# XOR.net
KiCad netlist of a schematic drawn in EAGLE
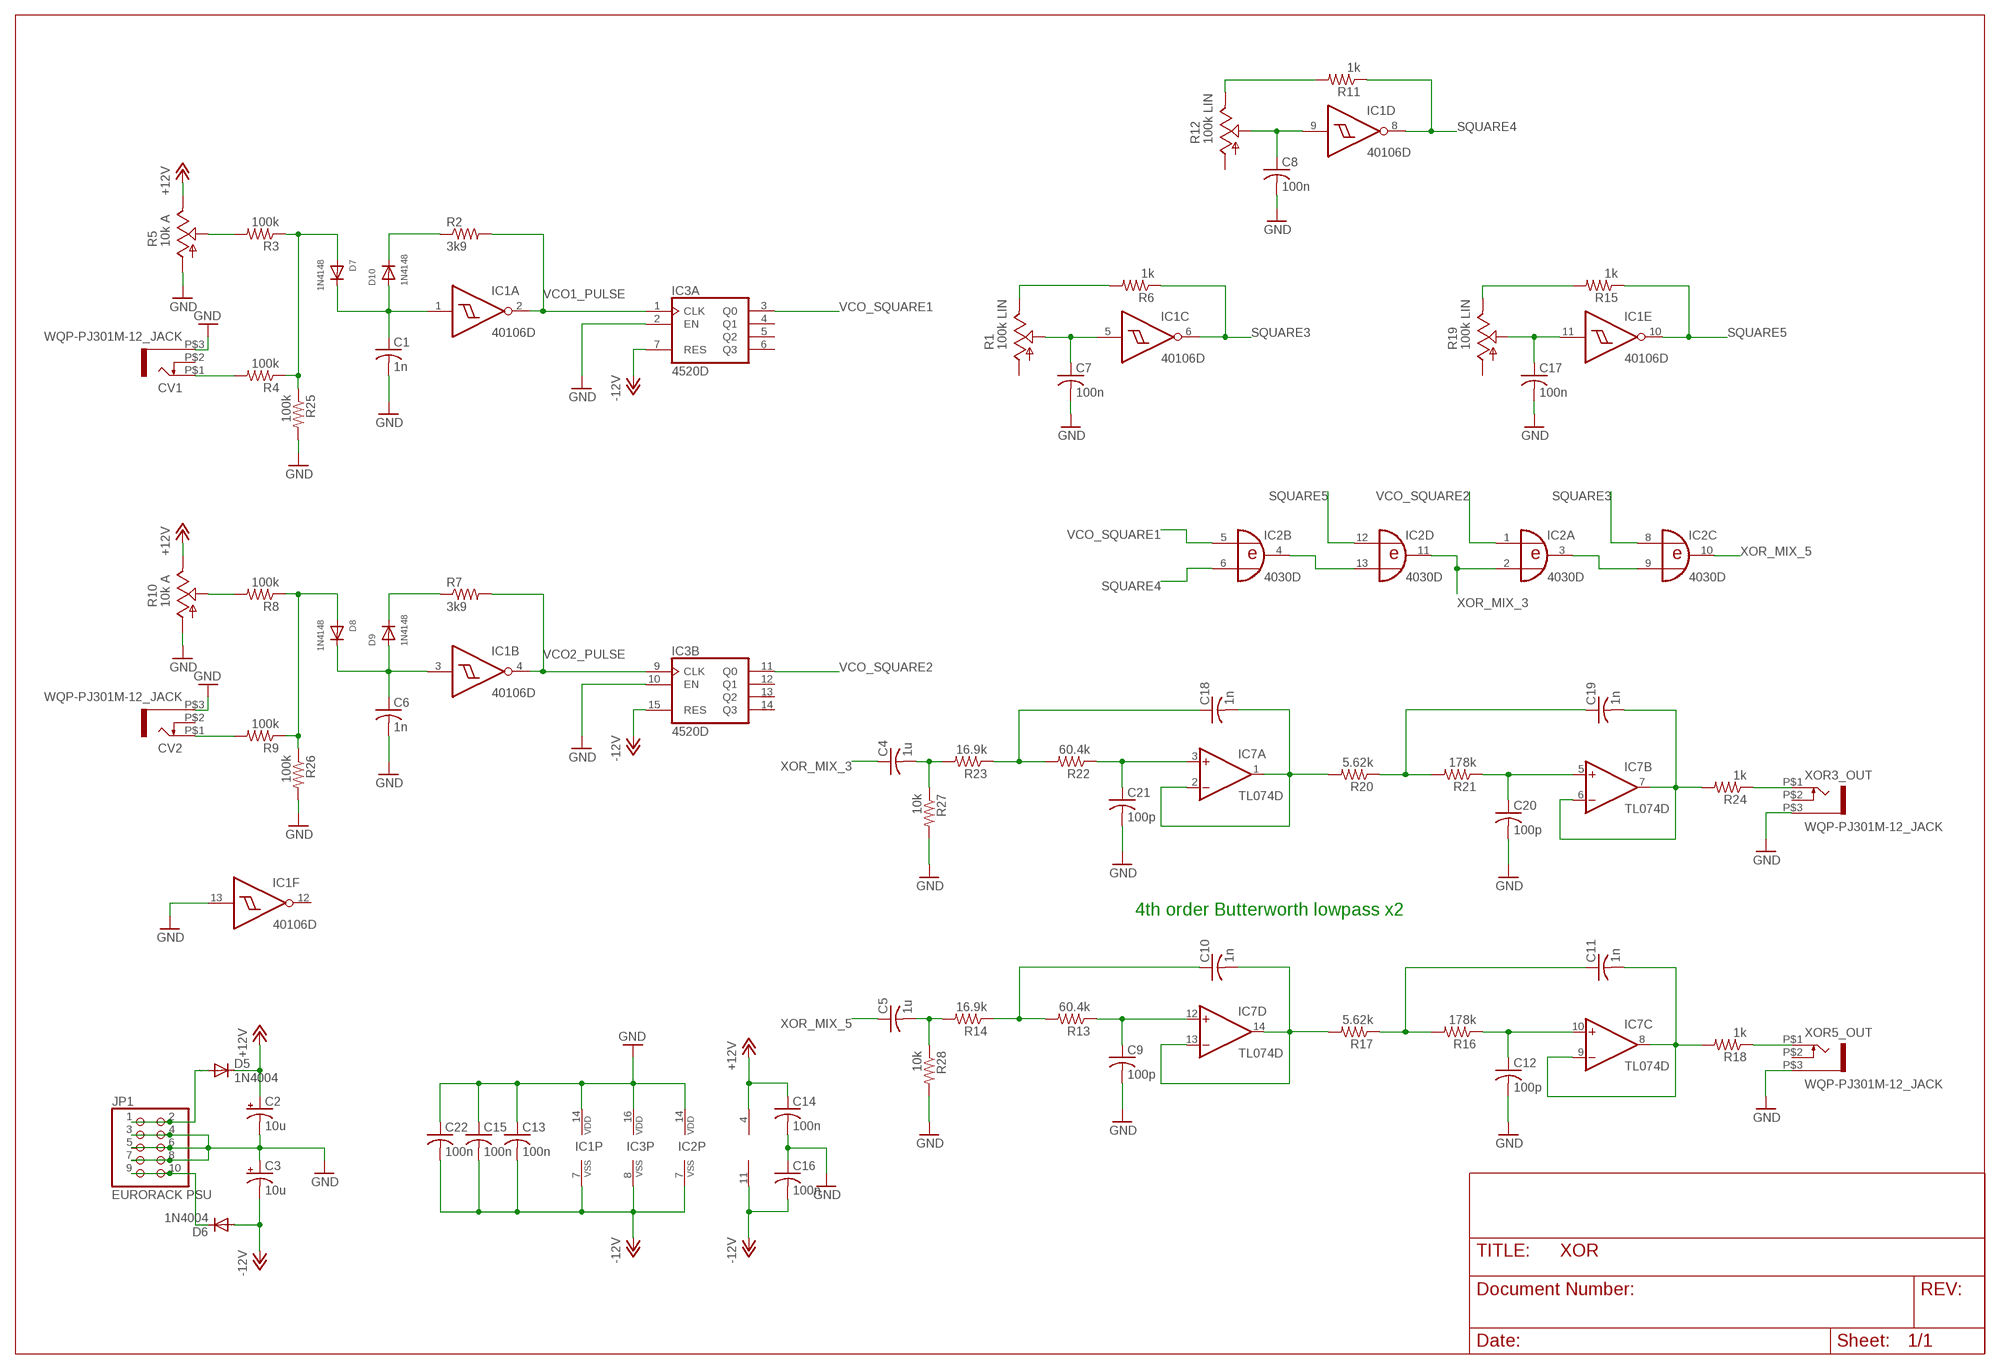
[diagram p0: schematic, sheet 1]

(export (version "E")
  (design (tool "Eeschema 10.0.6"))
  (components
    (comp (ref "C1")
      (value "1n")
      (footprint "eagle-import:C0603K")
      (libsource (lib "eagle-import") (part "C-USC0603K"))
    )
    (comp (ref "C2")
      (value "10u")
      (footprint "eagle-import:PANASONIC_D")
      (libsource (lib "eagle-import") (part "CPOL-USD"))
    )
    (comp (ref "C3")
      (value "10u")
      (footprint "eagle-import:PANASONIC_D")
      (libsource (lib "eagle-import") (part "CPOL-USD"))
    )
    (comp (ref "C4")
      (value "1u")
      (footprint "eagle-import:C0603K")
      (libsource (lib "eagle-import") (part "C-USC0603K"))
    )
    (comp (ref "C5")
      (value "1u")
      (footprint "eagle-import:C0603K")
      (libsource (lib "eagle-import") (part "C-USC0603K"))
    )
    (comp (ref "C6")
      (value "1n")
      (footprint "eagle-import:C0603K")
      (libsource (lib "eagle-import") (part "C-USC0603K"))
    )
    (comp (ref "C7")
      (value "100n")
      (footprint "eagle-import:C0603K")
      (libsource (lib "eagle-import") (part "C-USC0603K"))
    )
    (comp (ref "C8")
      (value "100n")
      (footprint "eagle-import:C0603K")
      (libsource (lib "eagle-import") (part "C-USC0603K"))
    )
    (comp (ref "C9")
      (value "100p")
      (footprint "eagle-import:C0603K")
      (libsource (lib "eagle-import") (part "C-USC0603K"))
    )
    (comp (ref "C10")
      (value "1n")
      (footprint "eagle-import:C0603K")
      (libsource (lib "eagle-import") (part "C-USC0603K"))
    )
    (comp (ref "C11")
      (value "1n")
      (footprint "eagle-import:C0603K")
      (libsource (lib "eagle-import") (part "C-USC0603K"))
    )
    (comp (ref "C12")
      (value "100p")
      (footprint "eagle-import:C0603K")
      (libsource (lib "eagle-import") (part "C-USC0603K"))
    )
    (comp (ref "C13")
      (value "100n")
      (footprint "eagle-import:C0603K")
      (libsource (lib "eagle-import") (part "C-USC0603K"))
    )
    (comp (ref "C14")
      (value "100n")
      (footprint "eagle-import:C0603K")
      (libsource (lib "eagle-import") (part "C-USC0603K"))
    )
    (comp (ref "C15")
      (value "100n")
      (footprint "eagle-import:C0603K")
      (libsource (lib "eagle-import") (part "C-USC0603K"))
    )
    (comp (ref "C16")
      (value "100n")
      (footprint "eagle-import:C0603K")
      (libsource (lib "eagle-import") (part "C-USC0603K"))
    )
    (comp (ref "C17")
      (value "100n")
      (footprint "eagle-import:C0603K")
      (libsource (lib "eagle-import") (part "C-USC0603K"))
    )
    (comp (ref "C18")
      (value "1n")
      (footprint "eagle-import:C0603K")
      (libsource (lib "eagle-import") (part "C-USC0603K"))
    )
    (comp (ref "C19")
      (value "1n")
      (footprint "eagle-import:C0603K")
      (libsource (lib "eagle-import") (part "C-USC0603K"))
    )
    (comp (ref "C20")
      (value "100p")
      (footprint "eagle-import:C0603K")
      (libsource (lib "eagle-import") (part "C-USC0603K"))
    )
    (comp (ref "C21")
      (value "100p")
      (footprint "eagle-import:C0603K")
      (libsource (lib "eagle-import") (part "C-USC0603K"))
    )
    (comp (ref "C22")
      (value "100n")
      (footprint "eagle-import:C0603K")
      (libsource (lib "eagle-import") (part "C-USC0603K"))
    )
    (comp (ref "CV1")
      (value "WQP-PJ301M-12_JACK")
      (footprint "eagle-import:WQP-PJ301M-12_JACK")
      (libsource (lib "eagle-import") (part "WQP-PJ301M-12_JACK"))
    )
    (comp (ref "CV2")
      (value "WQP-PJ301M-12_JACK")
      (footprint "eagle-import:WQP-PJ301M-12_JACK")
      (libsource (lib "eagle-import") (part "WQP-PJ301M-12_JACK"))
    )
    (comp (ref "D5")
      (value "1N4004")
      (footprint "eagle-import:DO214AA")
      (libsource (lib "eagle-import") (part "DIODE-DO214AA"))
    )
    (comp (ref "D6")
      (value "1N4004")
      (footprint "eagle-import:DO214AA")
      (libsource (lib "eagle-import") (part "DIODE-DO214AA"))
    )
    (comp (ref "D7")
      (value "1N4148")
      (footprint "eagle-import:SOD-323F")
      (libsource (lib "eagle-import") (part "DIODESOD-323F"))
    )
    (comp (ref "D8")
      (value "1N4148")
      (footprint "eagle-import:SOD-323F")
      (libsource (lib "eagle-import") (part "DIODESOD-323F"))
    )
    (comp (ref "D9")
      (value "1N4148")
      (footprint "eagle-import:SOD-323F")
      (libsource (lib "eagle-import") (part "DIODESOD-323F"))
    )
    (comp (ref "D10")
      (value "1N4148")
      (footprint "eagle-import:SOD-323F")
      (libsource (lib "eagle-import") (part "DIODESOD-323F"))
    )
    (comp (ref "IC1")
      (value "40106D")
      (footprint "eagle-import:SO14")
      (libsource (lib "eagle-import") (part "40106D"))
    )
    (comp (ref "IC2")
      (value "4030D")
      (footprint "eagle-import:SO14")
      (libsource (lib "eagle-import") (part "4030D"))
    )
    (comp (ref "IC3")
      (value "4520D")
      (footprint "eagle-import:SO16")
      (libsource (lib "eagle-import") (part "4520D"))
    )
    (comp (ref "IC7")
      (value "TL074D")
      (footprint "eagle-import:SO14")
      (libsource (lib "eagle-import") (part "TL074D"))
    )
    (comp (ref "JP1")
      (value "EURORACK PSU")
      (footprint "eagle-import:2X05")
      (libsource (lib "eagle-import") (part "PINHD-2X5"))
    )
    (comp (ref "R1")
      (value "100k LIN")
      (footprint "eagle-import:ALPS_POT_VERTICAL")
      (libsource (lib "eagle-import") (part "POT_USVERTICAL"))
    )
    (comp (ref "R2")
      (value "3k9")
      (footprint "eagle-import:R0603")
      (libsource (lib "eagle-import") (part "R-US_R0603"))
    )
    (comp (ref "R3")
      (value "100k")
      (footprint "eagle-import:R0603")
      (libsource (lib "eagle-import") (part "R-US_R0603"))
    )
    (comp (ref "R4")
      (value "100k")
      (footprint "eagle-import:R0603")
      (libsource (lib "eagle-import") (part "R-US_R0603"))
    )
    (comp (ref "R5")
      (value "10k A")
      (footprint "eagle-import:ALPS_POT_VERTICAL")
      (libsource (lib "eagle-import") (part "POT_USVERTICAL"))
    )
    (comp (ref "R6")
      (value "1k")
      (footprint "eagle-import:R0603")
      (libsource (lib "eagle-import") (part "R-US_R0603"))
    )
    (comp (ref "R7")
      (value "3k9")
      (footprint "eagle-import:R0603")
      (libsource (lib "eagle-import") (part "R-US_R0603"))
    )
    (comp (ref "R8")
      (value "100k")
      (footprint "eagle-import:R0603")
      (libsource (lib "eagle-import") (part "R-US_R0603"))
    )
    (comp (ref "R9")
      (value "100k")
      (footprint "eagle-import:R0603")
      (libsource (lib "eagle-import") (part "R-US_R0603"))
    )
    (comp (ref "R10")
      (value "10k A")
      (footprint "eagle-import:ALPS_POT_VERTICAL")
      (libsource (lib "eagle-import") (part "POT_USVERTICAL"))
    )
    (comp (ref "R11")
      (value "1k")
      (footprint "eagle-import:R0603")
      (libsource (lib "eagle-import") (part "R-US_R0603"))
    )
    (comp (ref "R12")
      (value "100k LIN")
      (footprint "eagle-import:ALPS_POT_VERTICAL")
      (libsource (lib "eagle-import") (part "POT_USVERTICAL"))
    )
    (comp (ref "R13")
      (value "60.4k")
      (footprint "eagle-import:R0603")
      (libsource (lib "eagle-import") (part "R-US_R0603"))
    )
    (comp (ref "R14")
      (value "16.9k")
      (footprint "eagle-import:R0603")
      (libsource (lib "eagle-import") (part "R-US_R0603"))
    )
    (comp (ref "R15")
      (value "1k")
      (footprint "eagle-import:R0603")
      (libsource (lib "eagle-import") (part "R-US_R0603"))
    )
    (comp (ref "R16")
      (value "178k")
      (footprint "eagle-import:R0603")
      (libsource (lib "eagle-import") (part "R-US_R0603"))
    )
    (comp (ref "R17")
      (value "5.62k")
      (footprint "eagle-import:R0603")
      (libsource (lib "eagle-import") (part "R-US_R0603"))
    )
    (comp (ref "R18")
      (value "1k")
      (footprint "eagle-import:R0603")
      (libsource (lib "eagle-import") (part "R-US_R0603"))
    )
    (comp (ref "R19")
      (value "100k LIN")
      (footprint "eagle-import:ALPS_POT_VERTICAL")
      (libsource (lib "eagle-import") (part "POT_USVERTICAL"))
    )
    (comp (ref "R20")
      (value "5.62k")
      (footprint "eagle-import:R0603")
      (libsource (lib "eagle-import") (part "R-US_R0603"))
    )
    (comp (ref "R21")
      (value "178k")
      (footprint "eagle-import:R0603")
      (libsource (lib "eagle-import") (part "R-US_R0603"))
    )
    (comp (ref "R22")
      (value "60.4k")
      (footprint "eagle-import:R0603")
      (libsource (lib "eagle-import") (part "R-US_R0603"))
    )
    (comp (ref "R23")
      (value "16.9k")
      (footprint "eagle-import:R0603")
      (libsource (lib "eagle-import") (part "R-US_R0603"))
    )
    (comp (ref "R24")
      (value "1k")
      (footprint "eagle-import:R0603")
      (libsource (lib "eagle-import") (part "R-US_R0603"))
    )
    (comp (ref "R25")
      (value "100k")
      (footprint "eagle-import:R0603")
      (libsource (lib "eagle-import") (part "R-US_R0603"))
    )
    (comp (ref "R26")
      (value "100k")
      (footprint "eagle-import:R0603")
      (libsource (lib "eagle-import") (part "R-US_R0603"))
    )
    (comp (ref "R27")
      (value "10k")
      (footprint "eagle-import:R0603")
      (libsource (lib "eagle-import") (part "R-US_R0603"))
    )
    (comp (ref "R28")
      (value "10k")
      (footprint "eagle-import:R0603")
      (libsource (lib "eagle-import") (part "R-US_R0603"))
    )
    (comp (ref "XOR3_OUT")
      (value "WQP-PJ301M-12_JACK")
      (footprint "eagle-import:WQP-PJ301M-12_JACK")
      (libsource (lib "eagle-import") (part "WQP-PJ301M-12_JACK"))
    )
    (comp (ref "XOR5_OUT")
      (value "WQP-PJ301M-12_JACK")
      (footprint "eagle-import:WQP-PJ301M-12_JACK")
      (libsource (lib "eagle-import") (part "WQP-PJ301M-12_JACK"))
    )
  )
  (nets
    (net (code "1") (name "+12V") (class "Default")
      (node (ref "C14") (pin "1") (pinfunction "1_1") (pintype "passive"))
      (node (ref "C2") (pin "+") (pinfunction "+_+") (pintype "passive"))
      (node (ref "D5") (pin "C") (pinfunction "C_C") (pintype "passive"))
      (node (ref "IC7") (pin "4") (pinfunction "V+_4") (pintype "power_in"))
      (node (ref "R10") (pin "P$1") (pinfunction "E_P$1") (pintype "passive"))
      (node (ref "R5") (pin "P$1") (pinfunction "E_P$1") (pintype "passive"))
    )
    (net (code "2") (name "-12V") (class "Default")
      (node (ref "C13") (pin "2") (pinfunction "2_2") (pintype "passive"))
      (node (ref "C15") (pin "2") (pinfunction "2_2") (pintype "passive"))
      (node (ref "C16") (pin "2") (pinfunction "2_2") (pintype "passive"))
      (node (ref "C22") (pin "2") (pinfunction "2_2") (pintype "passive"))
      (node (ref "C3") (pin "-") (pinfunction "-_-") (pintype "passive"))
      (node (ref "D6") (pin "A") (pinfunction "A_A") (pintype "passive"))
      (node (ref "IC1") (pin "7") (pinfunction "VSS_7") (pintype "power_in"))
      (node (ref "IC2") (pin "7") (pinfunction "VSS_7") (pintype "power_in"))
      (node (ref "IC3") (pin "15") (pinfunction "RES_15") (pintype "input"))
      (node (ref "IC3") (pin "7") (pinfunction "RES_7") (pintype "input"))
      (node (ref "IC3") (pin "8") (pinfunction "VSS_8") (pintype "power_in"))
      (node (ref "IC7") (pin "11") (pinfunction "V-_11") (pintype "power_in"))
    )
    (net (code "3") (name "/SQUARE3") (class "Default")
      (node (ref "IC1") (pin "6") (pinfunction "O_6") (pintype "output"))
      (node (ref "IC2") (pin "8") (pinfunction "I0_8") (pintype "input"))
      (node (ref "R6") (pin "1") (pinfunction "1_1") (pintype "passive"))
    )
    (net (code "4") (name "/SQUARE4") (class "Default")
      (node (ref "IC1") (pin "8") (pinfunction "O_8") (pintype "output"))
      (node (ref "IC2") (pin "6") (pinfunction "I1_6") (pintype "input"))
      (node (ref "R11") (pin "1") (pinfunction "1_1") (pintype "passive"))
    )
    (net (code "5") (name "/SQUARE5") (class "Default")
      (node (ref "IC1") (pin "10") (pinfunction "O_10") (pintype "output"))
      (node (ref "IC2") (pin "12") (pinfunction "I0_12") (pintype "input"))
      (node (ref "R15") (pin "1") (pinfunction "1_1") (pintype "passive"))
    )
    (net (code "6") (name "/VCO1_PULSE") (class "Default")
      (node (ref "IC1") (pin "2") (pinfunction "O_2") (pintype "output"))
      (node (ref "IC3") (pin "1") (pinfunction "CLK_1") (pintype "input"))
      (node (ref "R2") (pin "2") (pinfunction "2_2") (pintype "passive"))
    )
    (net (code "7") (name "/VCO2_PULSE") (class "Default")
      (node (ref "IC1") (pin "4") (pinfunction "O_4") (pintype "output"))
      (node (ref "IC3") (pin "9") (pinfunction "CLK_9") (pintype "input"))
      (node (ref "R7") (pin "2") (pinfunction "2_2") (pintype "passive"))
    )
    (net (code "8") (name "/VCO_SQUARE1") (class "Default")
      (node (ref "IC2") (pin "5") (pinfunction "I0_5") (pintype "input"))
      (node (ref "IC3") (pin "3") (pinfunction "Q0_3") (pintype "output"))
    )
    (net (code "9") (name "/VCO_SQUARE2") (class "Default")
      (node (ref "IC2") (pin "1") (pinfunction "I0_1") (pintype "input"))
      (node (ref "IC3") (pin "11") (pinfunction "Q0_11") (pintype "output"))
    )
    (net (code "10") (name "/XOR_MIX_3") (class "Default")
      (node (ref "C4") (pin "1") (pinfunction "1_1") (pintype "passive"))
      (node (ref "IC2") (pin "11") (pinfunction "O_11") (pintype "output"))
      (node (ref "IC2") (pin "2") (pinfunction "I1_2") (pintype "input"))
    )
    (net (code "11") (name "/XOR_MIX_5") (class "Default")
      (node (ref "C5") (pin "1") (pinfunction "1_1") (pintype "passive"))
      (node (ref "IC2") (pin "10") (pinfunction "O_10") (pintype "output"))
    )
    (net (code "12") (name "GND") (class "Default")
      (node (ref "C1") (pin "2") (pinfunction "2_2") (pintype "passive"))
      (node (ref "C12") (pin "2") (pinfunction "2_2") (pintype "passive"))
      (node (ref "C13") (pin "1") (pinfunction "1_1") (pintype "passive"))
      (node (ref "C14") (pin "2") (pinfunction "2_2") (pintype "passive"))
      (node (ref "C15") (pin "1") (pinfunction "1_1") (pintype "passive"))
      (node (ref "C16") (pin "1") (pinfunction "1_1") (pintype "passive"))
      (node (ref "C17") (pin "2") (pinfunction "2_2") (pintype "passive"))
      (node (ref "C2") (pin "-") (pinfunction "-_-") (pintype "passive"))
      (node (ref "C20") (pin "2") (pinfunction "2_2") (pintype "passive"))
      (node (ref "C21") (pin "2") (pinfunction "2_2") (pintype "passive"))
      (node (ref "C22") (pin "1") (pinfunction "1_1") (pintype "passive"))
      (node (ref "C3") (pin "+") (pinfunction "+_+") (pintype "passive"))
      (node (ref "C6") (pin "2") (pinfunction "2_2") (pintype "passive"))
      (node (ref "C7") (pin "2") (pinfunction "2_2") (pintype "passive"))
      (node (ref "C8") (pin "2") (pinfunction "2_2") (pintype "passive"))
      (node (ref "C9") (pin "2") (pinfunction "2_2") (pintype "passive"))
      (node (ref "CV1") (pin "P$3") (pinfunction "1_P$3") (pintype "passive"))
      (node (ref "CV2") (pin "P$3") (pinfunction "1_P$3") (pintype "passive"))
      (node (ref "IC1") (pin "13") (pinfunction "I_13") (pintype "input"))
      (node (ref "IC1") (pin "14") (pinfunction "VDD_14") (pintype "power_in"))
      (node (ref "IC2") (pin "14") (pinfunction "VDD_14") (pintype "power_in"))
      (node (ref "IC3") (pin "10") (pinfunction "EN_10") (pintype "input"))
      (node (ref "IC3") (pin "16") (pinfunction "VDD_16") (pintype "power_in"))
      (node (ref "IC3") (pin "2") (pinfunction "EN_2") (pintype "input"))
      (node (ref "JP1") (pin "3") (pinfunction "3_3") (pintype "passive"))
      (node (ref "JP1") (pin "4") (pinfunction "4_4") (pintype "passive"))
      (node (ref "JP1") (pin "5") (pinfunction "5_5") (pintype "passive"))
      (node (ref "JP1") (pin "6") (pinfunction "6_6") (pintype "passive"))
      (node (ref "JP1") (pin "7") (pinfunction "7_7") (pintype "passive"))
      (node (ref "JP1") (pin "8") (pinfunction "8_8") (pintype "passive"))
      (node (ref "R10") (pin "P$3") (pinfunction "A_P$3") (pintype "passive"))
      (node (ref "R25") (pin "2") (pinfunction "2_2") (pintype "passive"))
      (node (ref "R26") (pin "2") (pinfunction "2_2") (pintype "passive"))
      (node (ref "R27") (pin "2") (pinfunction "2_2") (pintype "passive"))
      (node (ref "R28") (pin "2") (pinfunction "2_2") (pintype "passive"))
      (node (ref "R5") (pin "P$3") (pinfunction "A_P$3") (pintype "passive"))
      (node (ref "XOR3_OUT") (pin "P$3") (pinfunction "1_P$3") (pintype "passive"))
      (node (ref "XOR5_OUT") (pin "P$3") (pinfunction "1_P$3") (pintype "passive"))
    )
    (net (code "13") (name "Net-(C4-Pad2)") (class "Default")
      (node (ref "C4") (pin "2") (pinfunction "2_2") (pintype "passive"))
      (node (ref "R23") (pin "2") (pinfunction "2_2") (pintype "passive"))
      (node (ref "R27") (pin "1") (pinfunction "1_1") (pintype "passive"))
    )
    (net (code "14") (name "Net-(C5-Pad2)") (class "Default")
      (node (ref "C5") (pin "2") (pinfunction "2_2") (pintype "passive"))
      (node (ref "R14") (pin "2") (pinfunction "2_2") (pintype "passive"))
      (node (ref "R28") (pin "1") (pinfunction "1_1") (pintype "passive"))
    )
    (net (code "15") (name "Net-(C10-Pad1)") (class "Default")
      (node (ref "C10") (pin "1") (pinfunction "1_1") (pintype "passive"))
      (node (ref "R13") (pin "2") (pinfunction "2_2") (pintype "passive"))
      (node (ref "R14") (pin "1") (pinfunction "1_1") (pintype "passive"))
    )
    (net (code "16") (name "Net-(C11-Pad1)") (class "Default")
      (node (ref "C11") (pin "1") (pinfunction "1_1") (pintype "passive"))
      (node (ref "R16") (pin "2") (pinfunction "2_2") (pintype "passive"))
      (node (ref "R17") (pin "1") (pinfunction "1_1") (pintype "passive"))
    )
    (net (code "17") (name "Net-(C18-Pad1)") (class "Default")
      (node (ref "C18") (pin "1") (pinfunction "1_1") (pintype "passive"))
      (node (ref "R22") (pin "2") (pinfunction "2_2") (pintype "passive"))
      (node (ref "R23") (pin "1") (pinfunction "1_1") (pintype "passive"))
    )
    (net (code "18") (name "Net-(C19-Pad1)") (class "Default")
      (node (ref "C19") (pin "1") (pinfunction "1_1") (pintype "passive"))
      (node (ref "R20") (pin "1") (pinfunction "1_1") (pintype "passive"))
      (node (ref "R21") (pin "2") (pinfunction "2_2") (pintype "passive"))
    )
    (net (code "19") (name "Net-(CV1-2)") (class "Default")
      (node (ref "CV1") (pin "P$1") (pinfunction "2_P$1") (pintype "passive"))
      (node (ref "R4") (pin "2") (pinfunction "2_2") (pintype "passive"))
    )
    (net (code "20") (name "Net-(CV2-2)") (class "Default")
      (node (ref "CV2") (pin "P$1") (pinfunction "2_P$1") (pintype "passive"))
      (node (ref "R9") (pin "2") (pinfunction "2_2") (pintype "passive"))
    )
    (net (code "21") (name "Net-(D5-PadA)") (class "Default")
      (node (ref "D5") (pin "A") (pinfunction "A_A") (pintype "passive"))
      (node (ref "JP1") (pin "1") (pinfunction "1_1") (pintype "passive"))
      (node (ref "JP1") (pin "2") (pinfunction "2_2") (pintype "passive"))
    )
    (net (code "22") (name "Net-(D6-PadC)") (class "Default")
      (node (ref "D6") (pin "C") (pinfunction "C_C") (pintype "passive"))
      (node (ref "JP1") (pin "10") (pinfunction "10_10") (pintype "passive"))
      (node (ref "JP1") (pin "9") (pinfunction "9_9") (pintype "passive"))
    )
    (net (code "23") (name "Net-(D7-PadA)") (class "Default")
      (node (ref "D7") (pin "A") (pinfunction "A_A") (pintype "passive"))
      (node (ref "R25") (pin "1") (pinfunction "1_1") (pintype "passive"))
      (node (ref "R3") (pin "1") (pinfunction "1_1") (pintype "passive"))
      (node (ref "R4") (pin "1") (pinfunction "1_1") (pintype "passive"))
    )
    (net (code "24") (name "Net-(D8-PadA)") (class "Default")
      (node (ref "D8") (pin "A") (pinfunction "A_A") (pintype "passive"))
      (node (ref "R26") (pin "1") (pinfunction "1_1") (pintype "passive"))
      (node (ref "R8") (pin "1") (pinfunction "1_1") (pintype "passive"))
      (node (ref "R9") (pin "1") (pinfunction "1_1") (pintype "passive"))
    )
    (net (code "25") (name "Net-(D9-PadC)") (class "Default")
      (node (ref "D9") (pin "C") (pinfunction "C_C") (pintype "passive"))
      (node (ref "R7") (pin "1") (pinfunction "1_1") (pintype "passive"))
    )
    (net (code "26") (name "Net-(D10-PadC)") (class "Default")
      (node (ref "D10") (pin "C") (pinfunction "C_C") (pintype "passive"))
      (node (ref "R2") (pin "1") (pinfunction "1_1") (pintype "passive"))
    )
    (net (code "27") (name "Net-(IC1A-I)") (class "Default")
      (node (ref "C1") (pin "1") (pinfunction "1_1") (pintype "passive"))
      (node (ref "D10") (pin "A") (pinfunction "A_A") (pintype "passive"))
      (node (ref "D7") (pin "C") (pinfunction "C_C") (pintype "passive"))
      (node (ref "IC1") (pin "1") (pinfunction "I_1") (pintype "input"))
    )
    (net (code "28") (name "Net-(IC1B-I)") (class "Default")
      (node (ref "C6") (pin "1") (pinfunction "1_1") (pintype "passive"))
      (node (ref "D8") (pin "C") (pinfunction "C_C") (pintype "passive"))
      (node (ref "D9") (pin "A") (pinfunction "A_A") (pintype "passive"))
      (node (ref "IC1") (pin "3") (pinfunction "I_3") (pintype "input"))
    )
    (net (code "29") (name "Net-(IC1C-I)") (class "Default")
      (node (ref "C7") (pin "1") (pinfunction "1_1") (pintype "passive"))
      (node (ref "IC1") (pin "5") (pinfunction "I_5") (pintype "input"))
      (node (ref "R1") (pin "P$2") (pinfunction "S_P$2") (pintype "passive"))
    )
    (net (code "30") (name "Net-(IC1D-I)") (class "Default")
      (node (ref "C8") (pin "1") (pinfunction "1_1") (pintype "passive"))
      (node (ref "IC1") (pin "9") (pinfunction "I_9") (pintype "input"))
      (node (ref "R12") (pin "P$2") (pinfunction "S_P$2") (pintype "passive"))
    )
    (net (code "31") (name "Net-(IC1E-I)") (class "Default")
      (node (ref "C17") (pin "1") (pinfunction "1_1") (pintype "passive"))
      (node (ref "IC1") (pin "11") (pinfunction "I_11") (pintype "input"))
      (node (ref "R19") (pin "P$2") (pinfunction "S_P$2") (pintype "passive"))
    )
    (net (code "32") (name "Net-(IC2A-O)") (class "Default")
      (node (ref "IC2") (pin "3") (pinfunction "O_3") (pintype "output"))
      (node (ref "IC2") (pin "9") (pinfunction "I1_9") (pintype "input"))
    )
    (net (code "33") (name "Net-(IC2B-O)") (class "Default")
      (node (ref "IC2") (pin "13") (pinfunction "I1_13") (pintype "input"))
      (node (ref "IC2") (pin "4") (pinfunction "O_4") (pintype "output"))
    )
    (net (code "34") (name "Net-(IC7A-+IN)") (class "Default")
      (node (ref "C21") (pin "1") (pinfunction "1_1") (pintype "passive"))
      (node (ref "IC7") (pin "3") (pinfunction "+IN_3") (pintype "input"))
      (node (ref "R22") (pin "1") (pinfunction "1_1") (pintype "passive"))
    )
    (net (code "35") (name "Net-(IC7A--IN)") (class "Default")
      (node (ref "C18") (pin "2") (pinfunction "2_2") (pintype "passive"))
      (node (ref "IC7") (pin "1") (pinfunction "OUT_1") (pintype "output"))
      (node (ref "IC7") (pin "2") (pinfunction "-IN_2") (pintype "input"))
      (node (ref "R20") (pin "2") (pinfunction "2_2") (pintype "passive"))
    )
    (net (code "36") (name "Net-(IC7B-+IN)") (class "Default")
      (node (ref "C20") (pin "1") (pinfunction "1_1") (pintype "passive"))
      (node (ref "IC7") (pin "5") (pinfunction "+IN_5") (pintype "input"))
      (node (ref "R21") (pin "1") (pinfunction "1_1") (pintype "passive"))
    )
    (net (code "37") (name "Net-(IC7B--IN)") (class "Default")
      (node (ref "C19") (pin "2") (pinfunction "2_2") (pintype "passive"))
      (node (ref "IC7") (pin "6") (pinfunction "-IN_6") (pintype "input"))
      (node (ref "IC7") (pin "7") (pinfunction "OUT_7") (pintype "output"))
      (node (ref "R24") (pin "2") (pinfunction "2_2") (pintype "passive"))
    )
    (net (code "38") (name "Net-(IC7C-+IN)") (class "Default")
      (node (ref "C12") (pin "1") (pinfunction "1_1") (pintype "passive"))
      (node (ref "IC7") (pin "10") (pinfunction "+IN_10") (pintype "input"))
      (node (ref "R16") (pin "1") (pinfunction "1_1") (pintype "passive"))
    )
    (net (code "39") (name "Net-(IC7C--IN)") (class "Default")
      (node (ref "C11") (pin "2") (pinfunction "2_2") (pintype "passive"))
      (node (ref "IC7") (pin "8") (pinfunction "OUT_8") (pintype "output"))
      (node (ref "IC7") (pin "9") (pinfunction "-IN_9") (pintype "input"))
      (node (ref "R18") (pin "2") (pinfunction "2_2") (pintype "passive"))
    )
    (net (code "40") (name "Net-(IC7D-+IN)") (class "Default")
      (node (ref "C9") (pin "1") (pinfunction "1_1") (pintype "passive"))
      (node (ref "IC7") (pin "12") (pinfunction "+IN_12") (pintype "input"))
      (node (ref "R13") (pin "1") (pinfunction "1_1") (pintype "passive"))
    )
    (net (code "41") (name "Net-(IC7D--IN)") (class "Default")
      (node (ref "C10") (pin "2") (pinfunction "2_2") (pintype "passive"))
      (node (ref "IC7") (pin "13") (pinfunction "-IN_13") (pintype "input"))
      (node (ref "IC7") (pin "14") (pinfunction "OUT_14") (pintype "output"))
      (node (ref "R17") (pin "2") (pinfunction "2_2") (pintype "passive"))
    )
    (net (code "42") (name "Net-(R1-E)") (class "Default")
      (node (ref "R1") (pin "P$1") (pinfunction "E_P$1") (pintype "passive"))
      (node (ref "R6") (pin "2") (pinfunction "2_2") (pintype "passive"))
    )
    (net (code "43") (name "Net-(R5-S)") (class "Default")
      (node (ref "R3") (pin "2") (pinfunction "2_2") (pintype "passive"))
      (node (ref "R5") (pin "P$2") (pinfunction "S_P$2") (pintype "passive"))
    )
    (net (code "44") (name "Net-(R10-S)") (class "Default")
      (node (ref "R10") (pin "P$2") (pinfunction "S_P$2") (pintype "passive"))
      (node (ref "R8") (pin "2") (pinfunction "2_2") (pintype "passive"))
    )
    (net (code "45") (name "Net-(R12-E)") (class "Default")
      (node (ref "R11") (pin "2") (pinfunction "2_2") (pintype "passive"))
      (node (ref "R12") (pin "P$1") (pinfunction "E_P$1") (pintype "passive"))
    )
    (net (code "46") (name "Net-(R19-E)") (class "Default")
      (node (ref "R15") (pin "2") (pinfunction "2_2") (pintype "passive"))
      (node (ref "R19") (pin "P$1") (pinfunction "E_P$1") (pintype "passive"))
    )
    (net (code "47") (name "Net-(XOR3_OUT-2)") (class "Default")
      (node (ref "R24") (pin "1") (pinfunction "1_1") (pintype "passive"))
      (node (ref "XOR3_OUT") (pin "P$1") (pinfunction "2_P$1") (pintype "passive"))
    )
    (net (code "48") (name "Net-(XOR5_OUT-2)") (class "Default")
      (node (ref "R18") (pin "1") (pinfunction "1_1") (pintype "passive"))
      (node (ref "XOR5_OUT") (pin "P$1") (pinfunction "2_P$1") (pintype "passive"))
    )
    (net (code "49") (name "unconnected-(CV1-3-PadP$2)") (class "Default")
      (node (ref "CV1") (pin "P$2") (pinfunction "3_P$2") (pintype "passive"))
    )
    (net (code "50") (name "unconnected-(CV2-3-PadP$2)") (class "Default")
      (node (ref "CV2") (pin "P$2") (pinfunction "3_P$2") (pintype "passive"))
    )
    (net (code "51") (name "unconnected-(IC1F-O-Pad12)") (class "Default")
      (node (ref "IC1") (pin "12") (pinfunction "O_12") (pintype "output"))
    )
    (net (code "52") (name "unconnected-(IC3A-Q1-Pad4)") (class "Default")
      (node (ref "IC3") (pin "4") (pinfunction "Q1_4") (pintype "output"))
    )
    (net (code "53") (name "unconnected-(IC3A-Q2-Pad5)") (class "Default")
      (node (ref "IC3") (pin "5") (pinfunction "Q2_5") (pintype "output"))
    )
    (net (code "54") (name "unconnected-(IC3A-Q3-Pad6)") (class "Default")
      (node (ref "IC3") (pin "6") (pinfunction "Q3_6") (pintype "output"))
    )
    (net (code "55") (name "unconnected-(IC3B-Q1-Pad12)") (class "Default")
      (node (ref "IC3") (pin "12") (pinfunction "Q1_12") (pintype "output"))
    )
    (net (code "56") (name "unconnected-(IC3B-Q2-Pad13)") (class "Default")
      (node (ref "IC3") (pin "13") (pinfunction "Q2_13") (pintype "output"))
    )
    (net (code "57") (name "unconnected-(IC3B-Q3-Pad14)") (class "Default")
      (node (ref "IC3") (pin "14") (pinfunction "Q3_14") (pintype "output"))
    )
    (net (code "58") (name "unconnected-(R1-A-PadP$3)") (class "Default")
      (node (ref "R1") (pin "P$3") (pinfunction "A_P$3") (pintype "passive"))
    )
    (net (code "59") (name "unconnected-(R12-A-PadP$3)") (class "Default")
      (node (ref "R12") (pin "P$3") (pinfunction "A_P$3") (pintype "passive"))
    )
    (net (code "60") (name "unconnected-(R19-A-PadP$3)") (class "Default")
      (node (ref "R19") (pin "P$3") (pinfunction "A_P$3") (pintype "passive"))
    )
    (net (code "61") (name "unconnected-(XOR3_OUT-3-PadP$2)") (class "Default")
      (node (ref "XOR3_OUT") (pin "P$2") (pinfunction "3_P$2") (pintype "passive"))
    )
    (net (code "62") (name "unconnected-(XOR5_OUT-3-PadP$2)") (class "Default")
      (node (ref "XOR5_OUT") (pin "P$2") (pinfunction "3_P$2") (pintype "passive"))
    )
  )
)
